# 11_SDRAM.net
KiCad netlist of a schematic drawn in Altium Designer
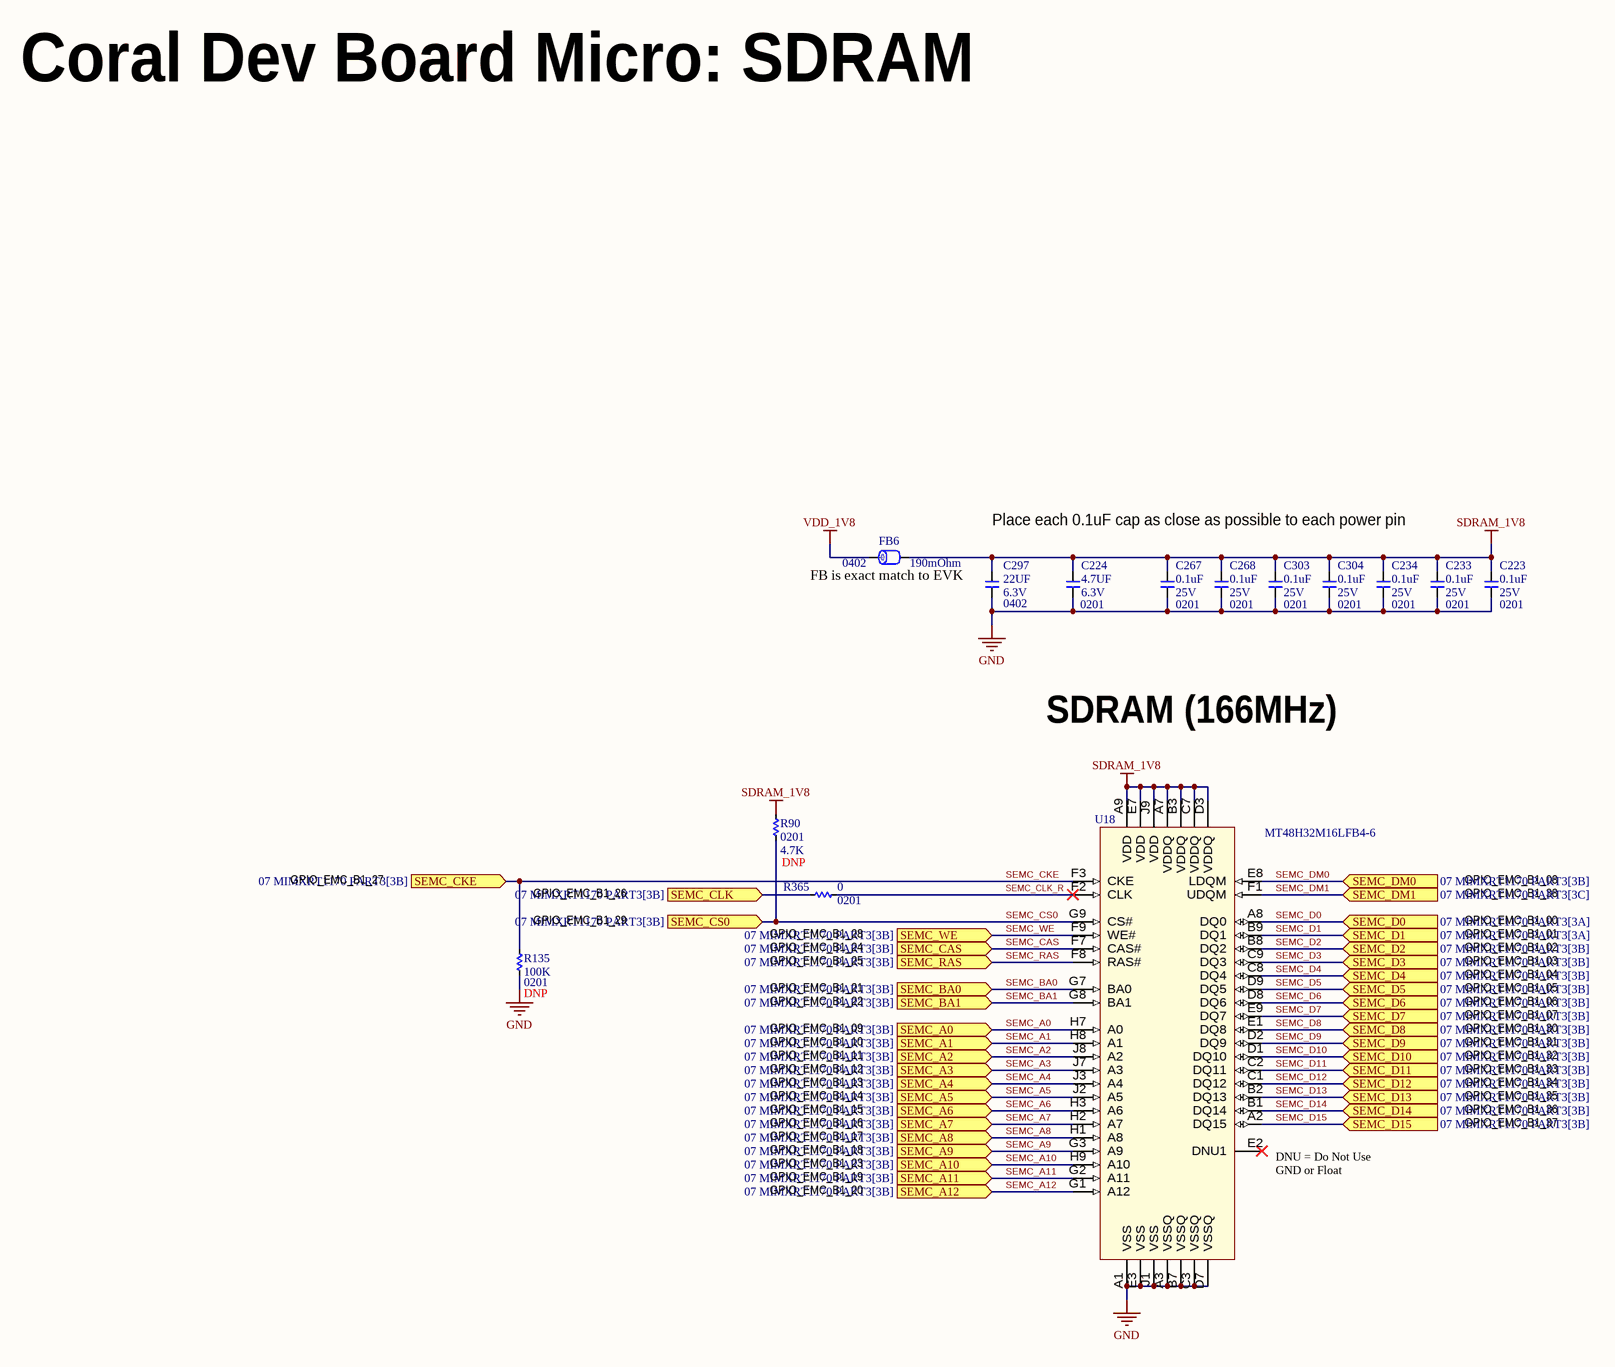
[diagram p0: 11 SDRAM.SchDoc]

(export (version "E")
  (design (tool "Eeschema 10.0.6"))
  (components
    (comp (ref "C223")
      (value "0.1uF")
      (footprint "C0201Y")
      (description "CAP, CER, X5R, 0.1uF, 25V, 20%, 0201, 0.33mm T")
      (fields
        (field (name "MFG") "MURATA")
        (field (name "PACKAGE") "0201")
        (field (name "VOLTAGE") "25V")
        (field (name "TOLERANCE") "20%")
      )
      (libsource (lib "AltiumReleaseLibDB") (part "__Template_Cap"))
    )
    (comp (ref "C224")
      (value "4.7UF")
      (footprint "C0201Y")
      (description "CAP, CER, X5R, 4.7uF, 20%, 6.3V, 0201")
      (fields
        (field (name "MFG") "MURATA")
        (field (name "PACKAGE") "0201")
        (field (name "VOLTAGE") "6.3V")
        (field (name "TOLERANCE") "20%")
      )
      (libsource (lib "AltiumReleaseLibDB") (part "__Template_Cap"))
    )
    (comp (ref "C233")
      (value "0.1uF")
      (footprint "C0201Y")
      (description "CAP, CER, X5R, 0.1uF, 25V, 20%, 0201, 0.33mm T")
      (fields
        (field (name "MFG") "MURATA")
        (field (name "PACKAGE") "0201")
        (field (name "VOLTAGE") "25V")
        (field (name "TOLERANCE") "20%")
      )
      (libsource (lib "AltiumReleaseLibDB") (part "__Template_Cap"))
    )
    (comp (ref "C234")
      (value "0.1uF")
      (footprint "C0201Y")
      (description "CAP, CER, X5R, 0.1uF, 25V, 20%, 0201, 0.33mm T")
      (fields
        (field (name "MFG") "MURATA")
        (field (name "PACKAGE") "0201")
        (field (name "VOLTAGE") "25V")
        (field (name "TOLERANCE") "20%")
      )
      (libsource (lib "AltiumReleaseLibDB") (part "__Template_Cap"))
    )
    (comp (ref "C267")
      (value "0.1uF")
      (footprint "C0201Y")
      (description "CAP, CER, X5R, 0.1uF, 25V, 20%, 0201, 0.33mm T")
      (fields
        (field (name "MFG") "MURATA")
        (field (name "PACKAGE") "0201")
        (field (name "VOLTAGE") "25V")
        (field (name "TOLERANCE") "20%")
      )
      (libsource (lib "AltiumReleaseLibDB") (part "__Template_Cap"))
    )
    (comp (ref "C268")
      (value "0.1uF")
      (footprint "C0201Y")
      (description "CAP, CER, X5R, 0.1uF, 25V, 20%, 0201, 0.33mm T")
      (fields
        (field (name "MFG") "MURATA")
        (field (name "PACKAGE") "0201")
        (field (name "VOLTAGE") "25V")
        (field (name "TOLERANCE") "20%")
      )
      (libsource (lib "AltiumReleaseLibDB") (part "__Template_Cap"))
    )
    (comp (ref "C297")
      (value "22UF")
      (footprint "C0402")
      (description "CAP, CER, X5R, 22uF, 20%, 6.3V, 0402")
      (fields
        (field (name "MFG") "AVX")
        (field (name "PACKAGE") "0402")
        (field (name "VOLTAGE") "6.3V")
        (field (name "TOLERANCE") "20%")
      )
      (libsource (lib "AltiumReleaseLibDB") (part "__Template_Cap"))
    )
    (comp (ref "C303")
      (value "0.1uF")
      (footprint "C0201Y")
      (description "CAP, CER, X5R, 0.1uF, 25V, 20%, 0201, 0.33mm T")
      (fields
        (field (name "MFG") "MURATA")
        (field (name "PACKAGE") "0201")
        (field (name "VOLTAGE") "25V")
        (field (name "TOLERANCE") "20%")
      )
      (libsource (lib "AltiumReleaseLibDB") (part "__Template_Cap"))
    )
    (comp (ref "C304")
      (value "0.1uF")
      (footprint "C0201Y")
      (description "CAP, CER, X5R, 0.1uF, 25V, 20%, 0201, 0.33mm T")
      (fields
        (field (name "MFG") "MURATA")
        (field (name "PACKAGE") "0201")
        (field (name "VOLTAGE") "25V")
        (field (name "TOLERANCE") "20%")
      )
      (libsource (lib "AltiumReleaseLibDB") (part "__Template_Cap"))
    )
    (comp (ref "FB6")
      (value "__Template_Ferrite_Bead")
      (footprint "L0402_H0.55MM")
      (description "FERRITE, BEAD, 120 OHMS@100MHZ, 25%, 550mA, 190 mOHM DCR, 0402")
      (fields
        (field (name "MFG") "Murata Electronics")
        (field (name "PACKAGE") "0402")
        (field (name "RDC MAX") "190mOhm")
      )
      (libsource (lib "AltiumReleaseLibDB") (part "__Template_Ferrite_Bead"))
    )
    (comp (ref "R90")
      (value "4.7K")
      (footprint "R0201")
      (description "RES, 4.7K, 5%, 1/20W, 0201")
      (fields
        (field (name "MFG") "YAGEO")
        (field (name "PACKAGE") "0201")
        (field (name "POWER") "1/20W")
        (field (name "DNP") "DNP")
      )
      (libsource (lib "AltiumReleaseLibDB") (part "__Template_Resistor"))
    )
    (comp (ref "R135")
      (value "100K")
      (footprint "R0201")
      (description "RES, 100K, 1%, 1/20W, 0201")
      (fields
        (field (name "MFG") "PANASONIC")
        (field (name "PACKAGE") "0201")
        (field (name "POWER") "1/20W")
        (field (name "DNP") "DNP")
      )
      (libsource (lib "AltiumReleaseLibDB") (part "__Template_Resistor"))
    )
    (comp (ref "R365")
      (value "0")
      (footprint "R0201")
      (description "RES, 0.0, 1/20W, 0201")
      (fields (field (name "MFG") "PANASONIC") (field (name "PACKAGE") "0201") (field (name "POWER") "1/20W"))
      (libsource (lib "AltiumReleaseLibDB") (part "__Template_Resistor"))
    )
    (comp (ref "U18")
      (value "SDRAM_MT48H32M16LFB4-6")
      (footprint "BGA54C80P6X9_800X800X100")
      (description "IC, MEMORY, MT48H32M16, VOLATILE, DRAM, 512Mb(32M x 16), 1.7 TO 1.95V VIN, VFBGA-54")
      (fields (field (name "MFG") "Micron Technology Inc.") (field (name "MFG P/N") "MT48H32M16LFB4-6"))
      (libsource (lib "AltiumReleaseLibDB") (part "SDRAM_MT48H32M16LFB4-6"))
    )
  )
  (nets
    (net (code "1") (name "/SEMC_A0") (class "Default")
      (node (ref "U18") (pin "H7") (pinfunction "A0_H7") (pintype "input"))
    )
    (net (code "2") (name "/SEMC_A1") (class "Default")
      (node (ref "U18") (pin "H8") (pinfunction "A1_H8") (pintype "input"))
    )
    (net (code "3") (name "/SEMC_A2") (class "Default")
      (node (ref "U18") (pin "J8") (pinfunction "A2_J8") (pintype "input"))
    )
    (net (code "4") (name "/SEMC_A3") (class "Default")
      (node (ref "U18") (pin "J7") (pinfunction "A3_J7") (pintype "input"))
    )
    (net (code "5") (name "/SEMC_A4") (class "Default")
      (node (ref "U18") (pin "J3") (pinfunction "A4_J3") (pintype "input"))
    )
    (net (code "6") (name "/SEMC_A5") (class "Default")
      (node (ref "U18") (pin "J2") (pinfunction "A5_J2") (pintype "input"))
    )
    (net (code "7") (name "/SEMC_A6") (class "Default")
      (node (ref "U18") (pin "H3") (pinfunction "A6_H3") (pintype "input"))
    )
    (net (code "8") (name "/SEMC_A7") (class "Default")
      (node (ref "U18") (pin "H2") (pinfunction "A7_H2") (pintype "input"))
    )
    (net (code "9") (name "/SEMC_A8") (class "Default")
      (node (ref "U18") (pin "H1") (pinfunction "A8_H1") (pintype "input"))
    )
    (net (code "10") (name "/SEMC_A9") (class "Default")
      (node (ref "U18") (pin "G3") (pinfunction "A9_G3") (pintype "input"))
    )
    (net (code "11") (name "/SEMC_A10") (class "Default")
      (node (ref "U18") (pin "H9") (pinfunction "A10_H9") (pintype "input"))
    )
    (net (code "12") (name "/SEMC_A11") (class "Default")
      (node (ref "U18") (pin "G2") (pinfunction "A11_G2") (pintype "input"))
    )
    (net (code "13") (name "/SEMC_A12") (class "Default")
      (node (ref "U18") (pin "G1") (pinfunction "A12_G1") (pintype "input"))
    )
    (net (code "14") (name "/SEMC_BA0") (class "Default")
      (node (ref "U18") (pin "G7") (pinfunction "BA0_G7") (pintype "input"))
    )
    (net (code "15") (name "/SEMC_BA1") (class "Default")
      (node (ref "U18") (pin "G8") (pinfunction "BA1_G8") (pintype "input"))
    )
    (net (code "16") (name "/SEMC_CAS") (class "Default")
      (node (ref "U18") (pin "F7") (pinfunction "CAS#_F7") (pintype "input"))
    )
    (net (code "17") (name "/SEMC_CKE") (class "Default")
      (node (ref "R135") (pin "2") (pintype "passive"))
      (node (ref "U18") (pin "F3") (pinfunction "CKE_F3") (pintype "input"))
    )
    (net (code "18") (name "/SEMC_CLK") (class "Default") (node (ref "R365") (pin "1") (pintype "passive")))
    (net (code "19") (name "/SEMC_CLK_R") (class "Default")
      (node (ref "R365") (pin "2") (pintype "passive"))
      (node (ref "U18") (pin "F2") (pinfunction "CLK_F2") (pintype "input"))
    )
    (net (code "20") (name "/SEMC_CS0") (class "Default")
      (node (ref "R90") (pin "1") (pintype "passive"))
      (node (ref "U18") (pin "G9") (pinfunction "CS#_G9") (pintype "input"))
    )
    (net (code "21") (name "/SEMC_D0") (class "Default")
      (node (ref "U18") (pin "A8") (pinfunction "DQ0_A8") (pintype "bidirectional"))
    )
    (net (code "22") (name "/SEMC_D1") (class "Default")
      (node (ref "U18") (pin "B9") (pinfunction "DQ1_B9") (pintype "bidirectional"))
    )
    (net (code "23") (name "/SEMC_D2") (class "Default")
      (node (ref "U18") (pin "B8") (pinfunction "DQ2_B8") (pintype "bidirectional"))
    )
    (net (code "24") (name "/SEMC_D3") (class "Default")
      (node (ref "U18") (pin "C9") (pinfunction "DQ3_C9") (pintype "bidirectional"))
    )
    (net (code "25") (name "/SEMC_D4") (class "Default")
      (node (ref "U18") (pin "C8") (pinfunction "DQ4_C8") (pintype "bidirectional"))
    )
    (net (code "26") (name "/SEMC_D5") (class "Default")
      (node (ref "U18") (pin "D9") (pinfunction "DQ5_D9") (pintype "bidirectional"))
    )
    (net (code "27") (name "/SEMC_D6") (class "Default")
      (node (ref "U18") (pin "D8") (pinfunction "DQ6_D8") (pintype "bidirectional"))
    )
    (net (code "28") (name "/SEMC_D7") (class "Default")
      (node (ref "U18") (pin "E9") (pinfunction "DQ7_E9") (pintype "bidirectional"))
    )
    (net (code "29") (name "/SEMC_D8") (class "Default")
      (node (ref "U18") (pin "E1") (pinfunction "DQ8_E1") (pintype "bidirectional"))
    )
    (net (code "30") (name "/SEMC_D9") (class "Default")
      (node (ref "U18") (pin "D2") (pinfunction "DQ9_D2") (pintype "bidirectional"))
    )
    (net (code "31") (name "/SEMC_D10") (class "Default")
      (node (ref "U18") (pin "D1") (pinfunction "DQ10_D1") (pintype "bidirectional"))
    )
    (net (code "32") (name "/SEMC_D11") (class "Default")
      (node (ref "U18") (pin "C2") (pinfunction "DQ11_C2") (pintype "bidirectional"))
    )
    (net (code "33") (name "/SEMC_D12") (class "Default")
      (node (ref "U18") (pin "C1") (pinfunction "DQ12_C1") (pintype "bidirectional"))
    )
    (net (code "34") (name "/SEMC_D13") (class "Default")
      (node (ref "U18") (pin "B2") (pinfunction "DQ13_B2") (pintype "bidirectional"))
    )
    (net (code "35") (name "/SEMC_D14") (class "Default")
      (node (ref "U18") (pin "B1") (pinfunction "DQ14_B1") (pintype "bidirectional"))
    )
    (net (code "36") (name "/SEMC_D15") (class "Default")
      (node (ref "U18") (pin "A2") (pinfunction "DQ15_A2") (pintype "bidirectional"))
    )
    (net (code "37") (name "/SEMC_DM0") (class "Default")
      (node (ref "U18") (pin "E8") (pinfunction "LDQM_E8") (pintype "input"))
    )
    (net (code "38") (name "/SEMC_DM1") (class "Default")
      (node (ref "U18") (pin "F1") (pinfunction "UDQM_F1") (pintype "input"))
    )
    (net (code "39") (name "/SEMC_RAS") (class "Default")
      (node (ref "U18") (pin "F8") (pinfunction "RAS#_F8") (pintype "input"))
    )
    (net (code "40") (name "/SEMC_WE") (class "Default")
      (node (ref "U18") (pin "F9") (pinfunction "WE#_F9") (pintype "input"))
    )
    (net (code "41") (name "GND") (class "Default")
      (node (ref "C223") (pin "2") (pintype "passive"))
      (node (ref "C224") (pin "2") (pintype "passive"))
      (node (ref "C233") (pin "2") (pintype "passive"))
      (node (ref "C234") (pin "2") (pintype "passive"))
      (node (ref "C267") (pin "2") (pintype "passive"))
      (node (ref "C268") (pin "2") (pintype "passive"))
      (node (ref "C297") (pin "2") (pintype "passive"))
      (node (ref "C303") (pin "2") (pintype "passive"))
      (node (ref "C304") (pin "2") (pintype "passive"))
      (node (ref "R135") (pin "1") (pintype "passive"))
      (node (ref "U18") (pin "A1") (pinfunction "VSS_A1") (pintype "power_in"))
      (node (ref "U18") (pin "A3") (pinfunction "VSSQ_A3") (pintype "power_in"))
      (node (ref "U18") (pin "B7") (pinfunction "VSSQ_B7") (pintype "power_in"))
      (node (ref "U18") (pin "C3") (pinfunction "VSSQ_C3") (pintype "power_in"))
      (node (ref "U18") (pin "D7") (pinfunction "VSSQ_D7") (pintype "power_in"))
      (node (ref "U18") (pin "E3") (pinfunction "VSS_E3") (pintype "power_in"))
      (node (ref "U18") (pin "J1") (pinfunction "VSS_J1") (pintype "power_in"))
    )
    (net (code "42") (name "SDRAM_1V8") (class "Default")
      (node (ref "C223") (pin "1") (pintype "passive"))
      (node (ref "C224") (pin "1") (pintype "passive"))
      (node (ref "C233") (pin "1") (pintype "passive"))
      (node (ref "C234") (pin "1") (pintype "passive"))
      (node (ref "C267") (pin "1") (pintype "passive"))
      (node (ref "C268") (pin "1") (pintype "passive"))
      (node (ref "C297") (pin "1") (pintype "passive"))
      (node (ref "C303") (pin "1") (pintype "passive"))
      (node (ref "C304") (pin "1") (pintype "passive"))
      (node (ref "FB6") (pin "2") (pinfunction "2_2") (pintype "passive"))
      (node (ref "R90") (pin "2") (pintype "passive"))
      (node (ref "U18") (pin "A7") (pinfunction "VDDQ_A7") (pintype "power_in"))
      (node (ref "U18") (pin "A9") (pinfunction "VDD_A9") (pintype "power_in"))
      (node (ref "U18") (pin "B3") (pinfunction "VDDQ_B3") (pintype "power_in"))
      (node (ref "U18") (pin "C7") (pinfunction "VDDQ_C7") (pintype "power_in"))
      (node (ref "U18") (pin "D3") (pinfunction "VDDQ_D3") (pintype "power_in"))
      (node (ref "U18") (pin "E7") (pinfunction "VDD_E7") (pintype "power_in"))
      (node (ref "U18") (pin "J9") (pinfunction "VDD_J9") (pintype "power_in"))
    )
    (net (code "43") (name "VDD_1V8") (class "Default")
      (node (ref "FB6") (pin "1") (pinfunction "1_1") (pintype "passive"))
    )
    (net (code "44") (name "unconnected-(U18-DNU1-PadE2)") (class "Default")
      (node (ref "U18") (pin "E2") (pinfunction "DNU1_E2") (pintype "passive+no_connect"))
    )
  )
)
